# ELC0205.net
KiCad netlist of a schematic drawn in Altium Designer
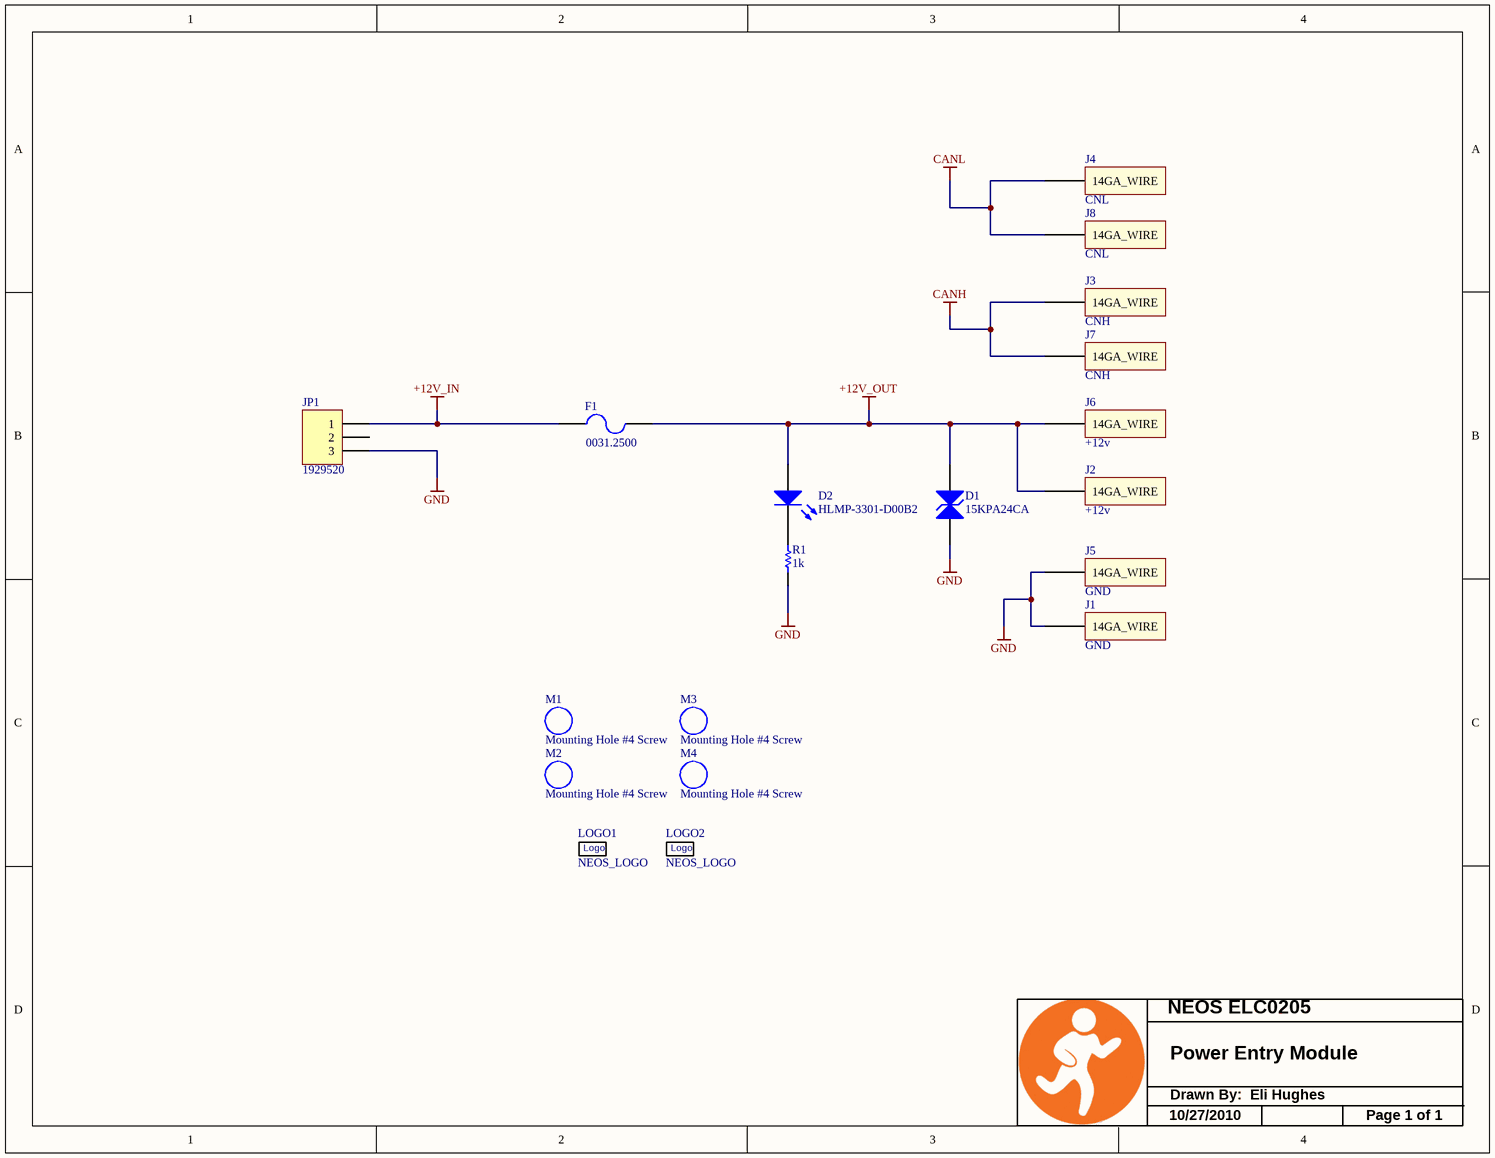
[diagram p0: ELC0205.SchDoc]

(export (version "E")
  (design (tool "Eeschema 10.0.6"))
  (components
    (comp (ref "D1")
      (value "15KPA24CA")
      (footprint "15KP")
      (description "15000W Axial Leaded Transient Voltage Suppressor")
      (fields
        (field (name "MANUFACTURER") "Littelfuse Inc")
        (field (name "MANUFACTURER PART NUMBER") "15KPA24CA-B")
      )
      (libsource (lib "Rays_Altium") (part "15KP"))
    )
    (comp (ref "D2")
      (value "HLMP-3301-D00B2")
      (footprint "LED-2")
      (description "LED 5MM GAP RED RT ANGLE HOUSING")
      (fields (field (name "MANUFACTURER") "Avago Technologies US Inc."))
      (libsource (lib "API") (part "LRDLN21RPHLP"))
    )
    (comp (ref "F1")
      (value "30A Fuse Holder")
      (footprint "Schurter 0031.2500")
      (description "Shock-Safe Fuseholder, 5 x 20 / 6.3 x 32 mm, Slot Knob, horizontal")
      (fields (field (name "MANUFACTURER") "Schurter") (field (name "MANUFACTURER PART NUMBER") "0031.2500"))
      (libsource (lib "Rays_Altium") (part "Fuse 2"))
    )
    (comp (ref "J1") (value "GND") (footprint "WIRE_14GA") (libsource (lib "") (part "~14GA_WIRE_1")))
    (comp (ref "J2") (value "+12v") (footprint "WIRE_14GA") (libsource (lib "API") (part "~14GA_WIRE")))
    (comp (ref "J3") (value "CNH") (footprint "WIRE_14GA") (libsource (lib "") (part "~14GA_WIRE_1")))
    (comp (ref "J4") (value "CNL") (footprint "WIRE_14GA") (libsource (lib "API") (part "~14GA_WIRE")))
    (comp (ref "J5") (value "GND") (footprint "WIRE_14GA") (libsource (lib "API") (part "~14GA_WIRE")))
    (comp (ref "J6") (value "+12v") (footprint "WIRE_14GA") (libsource (lib "API") (part "~14GA_WIRE")))
    (comp (ref "J7") (value "CNH") (footprint "WIRE_14GA") (libsource (lib "API") (part "~14GA_WIRE")))
    (comp (ref "J8") (value "CNL") (footprint "WIRE_14GA") (libsource (lib "API") (part "~14GA_WIRE")))
    (comp (ref "JP1")
      (value "1929520")
      (footprint "MKDS10")
      (description "Fixed Terminal Blocks MKDSP 10 HV/ 3-10.")
      (fields (field (name "MANUFACTURER") "Phoenix Contact"))
      (libsource (lib "Rays_Altium") (part "Header 3"))
    )
    (comp (ref "LOGO1")
      (value "NEOS_LOGO")
      (footprint "NEOS_LOGO_0")
      (libsource (lib "eLogo") (part "NEOS_LOGO"))
    )
    (comp (ref "LOGO2")
      (value "NEOS_LOGO")
      (footprint "FULL_LOGO_1")
      (libsource (lib "eLogo") (part "NEOS_LOGO"))
    )
    (comp (ref "M1")
      (value "Mounting Hole #4 Screw")
      (footprint "MHole#4")
      (libsource (lib "Rays_Altium") (part "MountingHole_4"))
    )
    (comp (ref "M2")
      (value "Mounting Hole #4 Screw")
      (footprint "MHole#4")
      (libsource (lib "Rays_Altium") (part "MountingHole_4"))
    )
    (comp (ref "M3")
      (value "Mounting Hole #4 Screw")
      (footprint "MHole#4")
      (libsource (lib "Rays_Altium") (part "MountingHole_4"))
    )
    (comp (ref "M4")
      (value "Mounting Hole #4 Screw")
      (footprint "MHole#4")
      (libsource (lib "Rays_Altium") (part "MountingHole_4"))
    )
    (comp (ref "R1")
      (value "1k")
      (footprint "R01M025 Axial 0.4")
      (description "RES 1.0K OHM CARBON FILM 1/4W 5%")
      (fields
        (field (name "MANUFACTURER") "Panasonic - ECG")
        (field (name "MANUFACTURER PART NUMBER") "ERD-S2TJ102V")
      )
      (libsource (lib "API") (part "R01M025"))
    )
  )
  (nets
    (net (code "1") (name "+12V_IN") (class "Default")
      (node (ref "F1") (pin "1") (pinfunction "1_1") (pintype "passive"))
      (node (ref "JP1") (pin "1") (pinfunction "1_1") (pintype "passive"))
    )
    (net (code "2") (name "+12V_OUT") (class "Default")
      (node (ref "D1") (pin "2") (pinfunction "K_2") (pintype "passive"))
      (node (ref "D2") (pin "1") (pinfunction "A_1") (pintype "passive"))
      (node (ref "F1") (pin "2") (pinfunction "2_2") (pintype "passive"))
      (node (ref "J2") (pin "1") (pinfunction "14GA_WIRE_1") (pintype "passive"))
      (node (ref "J6") (pin "1") (pinfunction "14GA_WIRE_1") (pintype "passive"))
    )
    (net (code "3") (name "CANH") (class "Default")
      (node (ref "J3") (pin "1") (pinfunction "14GA_WIRE_1") (pintype "passive"))
      (node (ref "J7") (pin "1") (pinfunction "14GA_WIRE_1") (pintype "passive"))
    )
    (net (code "4") (name "CANL") (class "Default")
      (node (ref "J4") (pin "1") (pinfunction "14GA_WIRE_1") (pintype "passive"))
      (node (ref "J8") (pin "1") (pinfunction "14GA_WIRE_1") (pintype "passive"))
    )
    (net (code "5") (name "GND") (class "Default")
      (node (ref "D1") (pin "1") (pinfunction "A_1") (pintype "passive"))
      (node (ref "J1") (pin "1") (pinfunction "14GA_WIRE_1") (pintype "passive"))
      (node (ref "J5") (pin "1") (pinfunction "14GA_WIRE_1") (pintype "passive"))
      (node (ref "JP1") (pin "3") (pinfunction "3_3") (pintype "passive"))
      (node (ref "R1") (pin "1") (pinfunction "1_1") (pintype "passive"))
    )
    (net (code "6") (name "Net-(D2-K)") (class "Default")
      (node (ref "D2") (pin "2") (pinfunction "K_2") (pintype "passive"))
      (node (ref "R1") (pin "2") (pinfunction "2_2") (pintype "passive"))
    )
    (net (code "7") (name "unconnected-(JP1-Pad2)") (class "Default")
      (node (ref "JP1") (pin "2") (pinfunction "2_2") (pintype "passive"))
    )
  )
)
